# nor.net
KiCad netlist of a schematic drawn in EAGLE
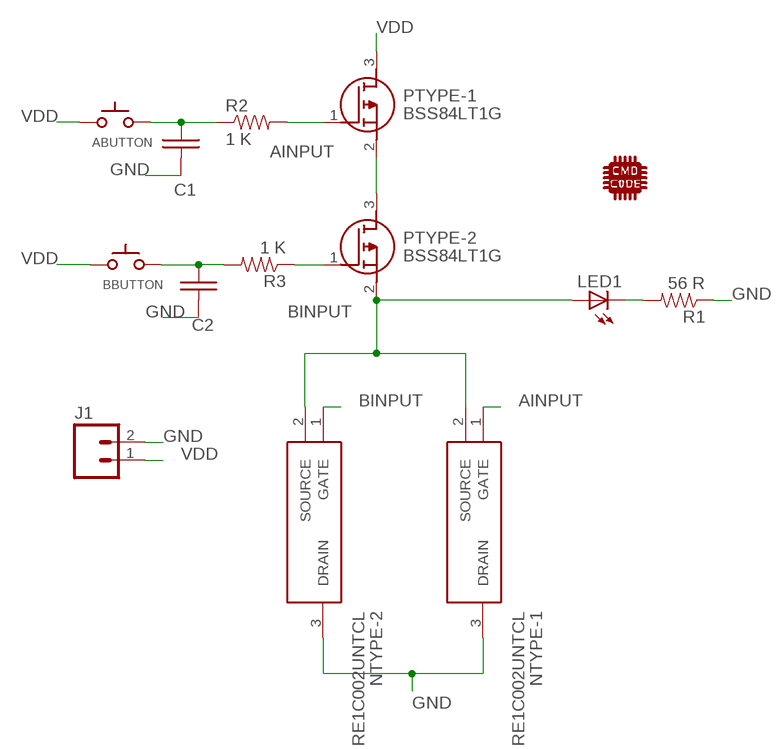
[diagram p0: schematic, sheet 1]

(export (version "E")
  (design (tool "Eeschema 10.0.6"))
  (components
    (comp (ref "ABUTTON")
      (value "SWITCH_TACTILETACTILE-2PIN-NARROW")
      (footprint "eagle-import:TACTILE-2PIN-NARROW")
      (libsource (lib "eagle-import") (part "SWITCH_TACTILETACTILE-2PIN-NARROW"))
    )
    (comp (ref "BBUTTON")
      (value "SWITCH_TACTILETACTILE-2PIN-NARROW")
      (footprint "eagle-import:TACTILE-2PIN-NARROW")
      (libsource (lib "eagle-import") (part "SWITCH_TACTILETACTILE-2PIN-NARROW"))
    )
    (comp (ref "C1")
      (value "C-USC1206")
      (footprint "eagle-import:C1206")
      (libsource (lib "eagle-import") (part "C-USC1206"))
    )
    (comp (ref "C2")
      (value "C-USC1206")
      (footprint "eagle-import:C1206")
      (libsource (lib "eagle-import") (part "C-USC1206"))
    )
    (comp (ref "J1")
      (value "M021X02_NO_SILK")
      (footprint "eagle-import:1X02_NO_SILK")
      (libsource (lib "eagle-import") (part "M021X02_NO_SILK"))
    )
    (comp (ref "LED1")
      (value "LED3MM")
      (footprint "eagle-import:LED3MM")
      (libsource (lib "eagle-import") (part "LED3MM"))
    )
    (comp (ref "NTYPE-1")
      (value "RE1C002UNTCL")
      (footprint "eagle-import:SOT50P160X85-3N")
      (fields (field (name "MOUSER_PART_NUMBER") "755-RE1C002UNTCL"))
      (libsource (lib "eagle-import") (part "RE1C002UNTCL"))
    )
    (comp (ref "NTYPE-2")
      (value "RE1C002UNTCL")
      (footprint "eagle-import:SOT50P160X85-3N")
      (fields (field (name "MOUSER_PART_NUMBER") "755-RE1C002UNTCL"))
      (libsource (lib "eagle-import") (part "RE1C002UNTCL"))
    )
    (comp (ref "PTYPE-1")
      (value "BSS84LT1G")
      (footprint "eagle-import:SOT96P237X111-3N")
      (fields (field (name "MOUSER_PART_NUMBER") "863-BSS84LT1G"))
      (libsource (lib "eagle-import") (part "BSS84LT1G"))
    )
    (comp (ref "PTYPE-2")
      (value "BSS84LT1G")
      (footprint "eagle-import:SOT96P237X111-3N")
      (fields (field (name "MOUSER_PART_NUMBER") "863-BSS84LT1G"))
      (libsource (lib "eagle-import") (part "BSS84LT1G"))
    )
    (comp (ref "R1")
      (value "56 R")
      (footprint "eagle-import:1206")
      (libsource (lib "eagle-import") (part "RESISTOR1206"))
    )
    (comp (ref "R2")
      (value "1 K")
      (footprint "eagle-import:0805")
      (libsource (lib "eagle-import") (part "RESISTOR0805-RES"))
    )
    (comp (ref "R3")
      (value "1 K")
      (footprint "eagle-import:0805")
      (libsource (lib "eagle-import") (part "RESISTOR0805-RES"))
    )
    (comp (ref "U$1")
      (value "CMD_C0DE_LOGOCMD_CODE_LOGO_TOP_COPPER")
      (footprint "eagle-import:CMD_C0DE_LOGO_TOP_COPPER")
      (libsource (lib "eagle-import") (part "CMD_C0DE_LOGOCMD_CODE_LOGO_TOP_COPPER"))
    )
  )
  (nets
    (net (code "1") (name "/AINPUT") (class "Default")
      (node (ref "NTYPE-1") (pin "1") (pinfunction "GATE_1") (pintype "bidirectional"))
      (node (ref "PTYPE-1") (pin "1") (pinfunction "G_1") (pintype "bidirectional"))
      (node (ref "R2") (pin "2") (pinfunction "2_2") (pintype "passive"))
    )
    (net (code "2") (name "/BINPUT") (class "Default")
      (node (ref "NTYPE-2") (pin "1") (pinfunction "GATE_1") (pintype "bidirectional"))
      (node (ref "PTYPE-2") (pin "1") (pinfunction "G_1") (pintype "bidirectional"))
      (node (ref "R3") (pin "1") (pinfunction "1_1") (pintype "passive"))
    )
    (net (code "3") (name "/GND") (class "Default")
      (node (ref "C1") (pin "2") (pinfunction "2_2") (pintype "passive"))
      (node (ref "C2") (pin "2") (pinfunction "2_2") (pintype "passive"))
      (node (ref "J1") (pin "2") (pinfunction "2_2") (pintype "passive"))
      (node (ref "NTYPE-1") (pin "3") (pinfunction "DRAIN_3") (pintype "input"))
      (node (ref "NTYPE-2") (pin "3") (pinfunction "DRAIN_3") (pintype "input"))
      (node (ref "R1") (pin "1") (pinfunction "1_1") (pintype "passive"))
    )
    (net (code "4") (name "/VDD") (class "Default")
      (node (ref "ABUTTON") (pin "P$2") (pinfunction "C_P$2") (pintype "passive"))
      (node (ref "BBUTTON") (pin "P$2") (pinfunction "C_P$2") (pintype "passive"))
      (node (ref "J1") (pin "1") (pinfunction "1_1") (pintype "passive"))
      (node (ref "PTYPE-1") (pin "3") (pinfunction "D_3") (pintype "bidirectional"))
    )
    (net (code "5") (name "Net-(ABUTTON-A)") (class "Default")
      (node (ref "ABUTTON") (pin "P$1") (pinfunction "A_P$1") (pintype "passive"))
      (node (ref "C1") (pin "1") (pinfunction "1_1") (pintype "passive"))
      (node (ref "R2") (pin "1") (pinfunction "1_1") (pintype "passive"))
    )
    (net (code "6") (name "Net-(BBUTTON-A)") (class "Default")
      (node (ref "BBUTTON") (pin "P$1") (pinfunction "A_P$1") (pintype "passive"))
      (node (ref "C2") (pin "1") (pinfunction "1_1") (pintype "passive"))
      (node (ref "R3") (pin "2") (pinfunction "2_2") (pintype "passive"))
    )
    (net (code "7") (name "Net-(LED1-C)") (class "Default")
      (node (ref "LED1") (pin "K") (pinfunction "C_K") (pintype "output"))
      (node (ref "R1") (pin "2") (pinfunction "2_2") (pintype "passive"))
    )
    (net (code "8") (name "Net-(NTYPE-1-SOURCE)") (class "Default")
      (node (ref "LED1") (pin "A") (pinfunction "A_A") (pintype "input"))
      (node (ref "NTYPE-1") (pin "2") (pinfunction "SOURCE_2") (pintype "bidirectional"))
      (node (ref "NTYPE-2") (pin "2") (pinfunction "SOURCE_2") (pintype "bidirectional"))
      (node (ref "PTYPE-2") (pin "2") (pinfunction "S_2") (pintype "bidirectional"))
    )
    (net (code "9") (name "Net-(PTYPE-1-S)") (class "Default")
      (node (ref "PTYPE-1") (pin "2") (pinfunction "S_2") (pintype "bidirectional"))
      (node (ref "PTYPE-2") (pin "3") (pinfunction "D_3") (pintype "bidirectional"))
    )
  )
)
